# pendulum.net
KiCad netlist of a schematic drawn in EAGLE
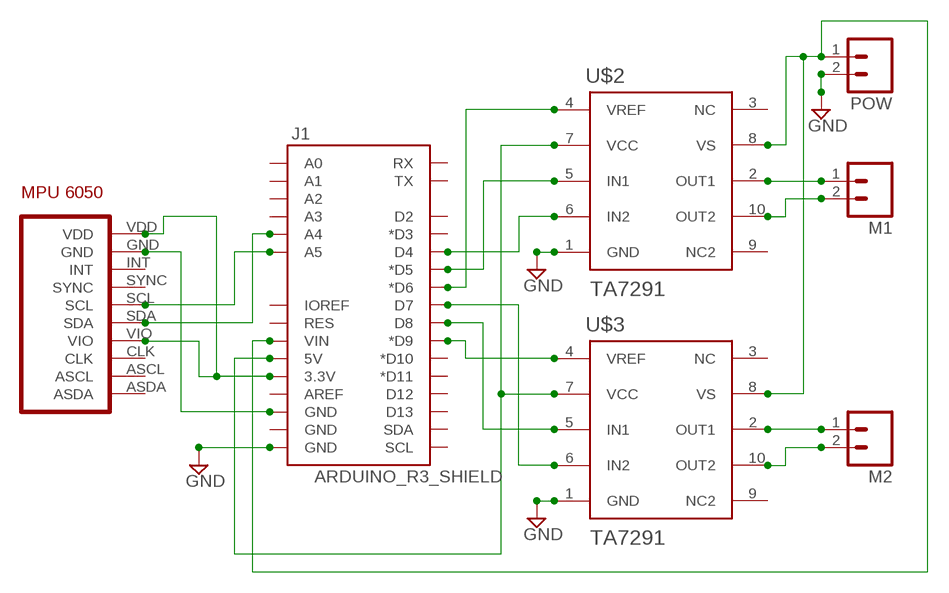
[diagram p0: schematic, sheet 1]

(export (version "E")
  (design (tool "Eeschema 10.0.6"))
  (components
    (comp (ref "J1")
      (value "ARDUINO_R3_SHIELD")
      (footprint "eagle-import:UNO_R3_SHIELD")
      (libsource (lib "eagle-import") (part "ARDUINO_R3_SHIELD"))
    )
    (comp (ref "M1")
      (value "M02LOCK_LONGPADS")
      (footprint "eagle-import:1X02_LOCK_LONGPADS")
      (libsource (lib "eagle-import") (part "M02LOCK_LONGPADS"))
    )
    (comp (ref "M2")
      (value "M02LOCK_LONGPADS")
      (footprint "eagle-import:1X02_LOCK_LONGPADS")
      (libsource (lib "eagle-import") (part "M02LOCK_LONGPADS"))
    )
    (comp (ref "POW")
      (value "M02LOCK_LONGPADS")
      (footprint "eagle-import:1X02_LOCK_LONGPADS")
      (libsource (lib "eagle-import") (part "M02LOCK_LONGPADS"))
    )
    (comp (ref "U$1")
      (value "MPU6050")
      (footprint "eagle-import:MPU6050")
      (libsource (lib "eagle-import") (part "MPU6050"))
    )
    (comp (ref "U$2")
      (value "TA7291")
      (footprint "eagle-import:HSIP10")
      (libsource (lib "eagle-import") (part "TA7291"))
    )
    (comp (ref "U$3")
      (value "TA7291")
      (footprint "eagle-import:HSIP10")
      (libsource (lib "eagle-import") (part "TA7291"))
    )
  )
  (nets
    (net (code "1") (name "GND") (class "Default")
      (node (ref "J1") (pin "GND@0") (pinfunction "GND_GND@0") (pintype "bidirectional"))
      (node (ref "POW") (pin "2") (pinfunction "2_2") (pintype "passive"))
      (node (ref "U$2") (pin "1") (pinfunction "GND_1") (pintype "bidirectional"))
      (node (ref "U$3") (pin "1") (pinfunction "GND_1") (pintype "bidirectional"))
    )
    (net (code "2") (name "Net-(J1-*D5)") (class "Default")
      (node (ref "J1") (pin "D5") (pinfunction "*D5_D5") (pintype "bidirectional"))
      (node (ref "U$2") (pin "5") (pinfunction "IN1_5") (pintype "bidirectional"))
    )
    (net (code "3") (name "Net-(J1-*D6)") (class "Default")
      (node (ref "J1") (pin "D6") (pinfunction "*D6_D6") (pintype "bidirectional"))
      (node (ref "U$2") (pin "4") (pinfunction "VREF_4") (pintype "bidirectional"))
    )
    (net (code "4") (name "Net-(J1-*D9)") (class "Default")
      (node (ref "J1") (pin "D9") (pinfunction "*D9_D9") (pintype "bidirectional"))
      (node (ref "U$3") (pin "4") (pinfunction "VREF_4") (pintype "bidirectional"))
    )
    (net (code "5") (name "Net-(J1-GND-PadGND@2)") (class "Default")
      (node (ref "J1") (pin "GND@2") (pinfunction "GND_GND@2") (pintype "bidirectional"))
      (node (ref "U$1") (pin "GND") (pinfunction "GND_GND") (pintype "bidirectional"))
    )
    (net (code "6") (name "Net-(J1-Pad3.3V)") (class "Default")
      (node (ref "J1") (pin "3.3V") (pinfunction "3.3V_3.3V") (pintype "bidirectional"))
      (node (ref "U$1") (pin "VDD") (pinfunction "VDD_VDD") (pintype "bidirectional"))
      (node (ref "U$1") (pin "VIO") (pinfunction "VIO_VIO") (pintype "bidirectional"))
    )
    (net (code "7") (name "Net-(J1-PadA4)") (class "Default")
      (node (ref "J1") (pin "A4") (pinfunction "A4_A4") (pintype "bidirectional"))
      (node (ref "U$1") (pin "SDA") (pinfunction "SDA_SDA") (pintype "bidirectional"))
    )
    (net (code "8") (name "Net-(J1-PadA5)") (class "Default")
      (node (ref "J1") (pin "A5") (pinfunction "A5_A5") (pintype "bidirectional"))
      (node (ref "U$1") (pin "SCL") (pinfunction "SCL_SCL") (pintype "bidirectional"))
    )
    (net (code "9") (name "Net-(U$2-IN2)") (class "Default")
      (node (ref "J1") (pin "D4") (pinfunction "D4_D4") (pintype "bidirectional"))
      (node (ref "U$2") (pin "6") (pinfunction "IN2_6") (pintype "bidirectional"))
    )
    (net (code "10") (name "Net-(U$2-OUT1)") (class "Default")
      (node (ref "M1") (pin "1") (pinfunction "1_1") (pintype "passive"))
      (node (ref "U$2") (pin "2") (pinfunction "OUT1_2") (pintype "bidirectional"))
    )
    (net (code "11") (name "Net-(U$2-OUT2)") (class "Default")
      (node (ref "M1") (pin "2") (pinfunction "2_2") (pintype "passive"))
      (node (ref "U$2") (pin "10") (pinfunction "OUT2_10") (pintype "bidirectional"))
    )
    (net (code "12") (name "Net-(U$2-VCC)") (class "Default")
      (node (ref "J1") (pin "5V") (pinfunction "5V_5V") (pintype "bidirectional"))
      (node (ref "U$2") (pin "7") (pinfunction "VCC_7") (pintype "bidirectional"))
      (node (ref "U$3") (pin "7") (pinfunction "VCC_7") (pintype "bidirectional"))
    )
    (net (code "13") (name "Net-(U$2-VS)") (class "Default")
      (node (ref "J1") (pin "VIN") (pinfunction "VIN_VIN") (pintype "bidirectional"))
      (node (ref "POW") (pin "1") (pinfunction "1_1") (pintype "passive"))
      (node (ref "U$2") (pin "8") (pinfunction "VS_8") (pintype "bidirectional"))
      (node (ref "U$3") (pin "8") (pinfunction "VS_8") (pintype "bidirectional"))
    )
    (net (code "14") (name "Net-(U$3-IN1)") (class "Default")
      (node (ref "J1") (pin "D8") (pinfunction "D8_D8") (pintype "bidirectional"))
      (node (ref "U$3") (pin "5") (pinfunction "IN1_5") (pintype "bidirectional"))
    )
    (net (code "15") (name "Net-(U$3-IN2)") (class "Default")
      (node (ref "J1") (pin "D7") (pinfunction "D7_D7") (pintype "bidirectional"))
      (node (ref "U$3") (pin "6") (pinfunction "IN2_6") (pintype "bidirectional"))
    )
    (net (code "16") (name "Net-(U$3-OUT1)") (class "Default")
      (node (ref "M2") (pin "1") (pinfunction "1_1") (pintype "passive"))
      (node (ref "U$3") (pin "2") (pinfunction "OUT1_2") (pintype "bidirectional"))
    )
    (net (code "17") (name "Net-(U$3-OUT2)") (class "Default")
      (node (ref "M2") (pin "2") (pinfunction "2_2") (pintype "passive"))
      (node (ref "U$3") (pin "10") (pinfunction "OUT2_10") (pintype "bidirectional"))
    )
    (net (code "18") (name "unconnected-(J1-*D3-PadD3)") (class "Default")
      (node (ref "J1") (pin "D3") (pinfunction "*D3_D3") (pintype "bidirectional"))
    )
    (net (code "19") (name "unconnected-(J1-*D10-PadD10)") (class "Default")
      (node (ref "J1") (pin "D10") (pinfunction "*D10_D10") (pintype "bidirectional"))
    )
    (net (code "20") (name "unconnected-(J1-*D11-PadD11)") (class "Default")
      (node (ref "J1") (pin "D11") (pinfunction "*D11_D11") (pintype "bidirectional"))
    )
    (net (code "21") (name "unconnected-(J1-GND-PadGND@1)") (class "Default")
      (node (ref "J1") (pin "GND@1") (pinfunction "GND_GND@1") (pintype "bidirectional"))
    )
    (net (code "22") (name "unconnected-(J1-PadA0)") (class "Default")
      (node (ref "J1") (pin "A0") (pinfunction "A0_A0") (pintype "bidirectional"))
    )
    (net (code "23") (name "unconnected-(J1-PadA1)") (class "Default")
      (node (ref "J1") (pin "A1") (pinfunction "A1_A1") (pintype "bidirectional"))
    )
    (net (code "24") (name "unconnected-(J1-PadA2)") (class "Default")
      (node (ref "J1") (pin "A2") (pinfunction "A2_A2") (pintype "bidirectional"))
    )
    (net (code "25") (name "unconnected-(J1-PadA3)") (class "Default")
      (node (ref "J1") (pin "A3") (pinfunction "A3_A3") (pintype "bidirectional"))
    )
    (net (code "26") (name "unconnected-(J1-PadAREF)") (class "Default")
      (node (ref "J1") (pin "AREF") (pinfunction "AREF_AREF") (pintype "bidirectional"))
    )
    (net (code "27") (name "unconnected-(J1-PadD2)") (class "Default")
      (node (ref "J1") (pin "D2") (pinfunction "D2_D2") (pintype "bidirectional"))
    )
    (net (code "28") (name "unconnected-(J1-PadD12)") (class "Default")
      (node (ref "J1") (pin "D12") (pinfunction "D12_D12") (pintype "bidirectional"))
    )
    (net (code "29") (name "unconnected-(J1-PadD13)") (class "Default")
      (node (ref "J1") (pin "D13") (pinfunction "D13_D13") (pintype "bidirectional"))
    )
    (net (code "30") (name "unconnected-(J1-PadIOREF)") (class "Default")
      (node (ref "J1") (pin "IOREF") (pinfunction "IOREF_IOREF") (pintype "bidirectional"))
    )
    (net (code "31") (name "unconnected-(J1-PadRES)") (class "Default")
      (node (ref "J1") (pin "RES") (pinfunction "RES_RES") (pintype "bidirectional"))
    )
    (net (code "32") (name "unconnected-(J1-PadRX)") (class "Default")
      (node (ref "J1") (pin "RX") (pinfunction "RX_RX") (pintype "bidirectional"))
    )
    (net (code "33") (name "unconnected-(J1-PadSCL)") (class "Default")
      (node (ref "J1") (pin "SCL") (pinfunction "SCL_SCL") (pintype "bidirectional"))
    )
    (net (code "34") (name "unconnected-(J1-PadSDA)") (class "Default")
      (node (ref "J1") (pin "SDA") (pinfunction "SDA_SDA") (pintype "bidirectional"))
    )
    (net (code "35") (name "unconnected-(J1-PadTX)") (class "Default")
      (node (ref "J1") (pin "TX") (pinfunction "TX_TX") (pintype "bidirectional"))
    )
    (net (code "36") (name "unconnected-(U$1-PadASCL)") (class "Default")
      (node (ref "U$1") (pin "ASCL") (pinfunction "ASCL_ASCL") (pintype "bidirectional"))
    )
    (net (code "37") (name "unconnected-(U$1-PadASDA)") (class "Default")
      (node (ref "U$1") (pin "ASDA") (pinfunction "ASDA_ASDA") (pintype "bidirectional"))
    )
    (net (code "38") (name "unconnected-(U$1-PadCLK)") (class "Default")
      (node (ref "U$1") (pin "CLK") (pinfunction "CLK_CLK") (pintype "bidirectional"))
    )
    (net (code "39") (name "unconnected-(U$1-PadINT)") (class "Default")
      (node (ref "U$1") (pin "INT") (pinfunction "INT_INT") (pintype "bidirectional"))
    )
    (net (code "40") (name "unconnected-(U$1-PadSYNC)") (class "Default")
      (node (ref "U$1") (pin "SYNC") (pinfunction "SYNC_SYNC") (pintype "bidirectional"))
    )
    (net (code "41") (name "unconnected-(U$2-NC-Pad3)") (class "Default")
      (node (ref "U$2") (pin "3") (pinfunction "NC_3") (pintype "bidirectional"))
    )
    (net (code "42") (name "unconnected-(U$2-NC2-Pad9)") (class "Default")
      (node (ref "U$2") (pin "9") (pinfunction "NC2_9") (pintype "bidirectional"))
    )
    (net (code "43") (name "unconnected-(U$3-NC-Pad3)") (class "Default")
      (node (ref "U$3") (pin "3") (pinfunction "NC_3") (pintype "bidirectional"))
    )
    (net (code "44") (name "unconnected-(U$3-NC2-Pad9)") (class "Default")
      (node (ref "U$3") (pin "9") (pinfunction "NC2_9") (pintype "bidirectional"))
    )
  )
)
